# ESP-Live.net
KiCad netlist of a schematic drawn in EAGLE
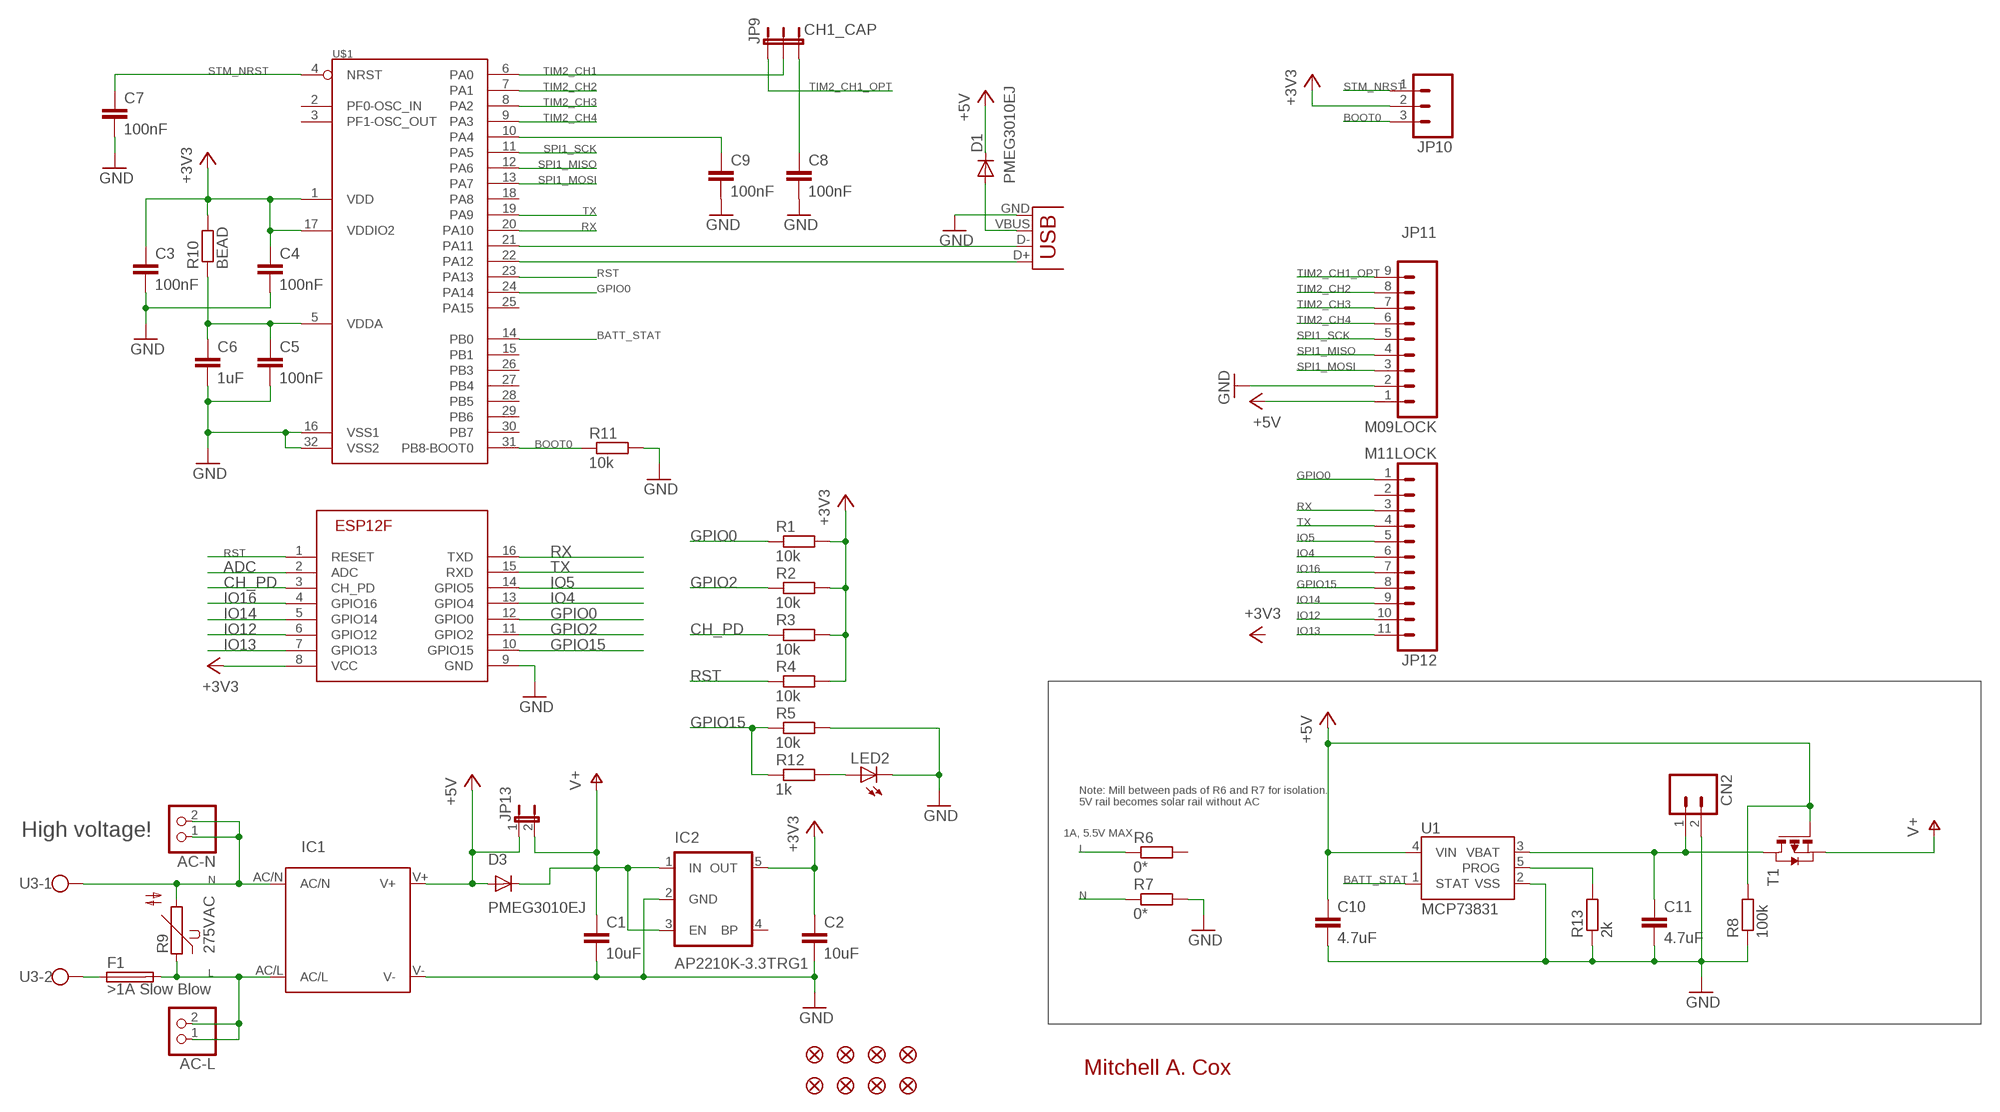
[diagram p0: schematic, sheet 1]

(export (version "E")
  (design (tool "Eeschema 10.0.6"))
  (components
    (comp (ref "AC-L")
      (value "PINHD-1X2")
      (footprint "eagle-import:1X02")
      (libsource (lib "eagle-import") (part "PINHD-1X2"))
    )
    (comp (ref "AC-N")
      (value "PINHD-1X2")
      (footprint "eagle-import:1X02")
      (libsource (lib "eagle-import") (part "PINHD-1X2"))
    )
    (comp (ref "C1")
      (value "10uF")
      (footprint "eagle-import:C0805")
      (libsource (lib "eagle-import") (part "C-EUC0805"))
    )
    (comp (ref "C2")
      (value "10uF")
      (footprint "eagle-import:C0805")
      (libsource (lib "eagle-import") (part "C-EUC0805"))
    )
    (comp (ref "C3")
      (value "100nF")
      (footprint "eagle-import:C0603")
      (libsource (lib "eagle-import") (part "C-EUC0603"))
    )
    (comp (ref "C4")
      (value "100nF")
      (footprint "eagle-import:C0603")
      (libsource (lib "eagle-import") (part "C-EUC0603"))
    )
    (comp (ref "C5")
      (value "100nF")
      (footprint "eagle-import:C0603")
      (libsource (lib "eagle-import") (part "C-EUC0603"))
    )
    (comp (ref "C6")
      (value "1uF")
      (footprint "eagle-import:C0805")
      (libsource (lib "eagle-import") (part "C-EUC0805"))
    )
    (comp (ref "C7")
      (value "100nF")
      (footprint "eagle-import:C0603")
      (libsource (lib "eagle-import") (part "C-EUC0603"))
    )
    (comp (ref "C8")
      (value "100nF")
      (footprint "eagle-import:C0603")
      (libsource (lib "eagle-import") (part "C-EUC0603"))
    )
    (comp (ref "C9")
      (value "100nF")
      (footprint "eagle-import:C0603")
      (libsource (lib "eagle-import") (part "C-EUC0603"))
    )
    (comp (ref "C10")
      (value "4.7uF")
      (footprint "eagle-import:C0805")
      (libsource (lib "eagle-import") (part "C-EUC0805"))
    )
    (comp (ref "C11")
      (value "4.7uF")
      (footprint "eagle-import:C0805")
      (libsource (lib "eagle-import") (part "C-EUC0805"))
    )
    (comp (ref "CN1")
      (value "USBSMD")
      (footprint "eagle-import:USB-MINIB")
      (libsource (lib "eagle-import") (part "USBSMD"))
    )
    (comp (ref "CN2")
      (value "M02-JST-2-PTH-NO_SILK")
      (footprint "eagle-import:JST-2-PTH-NS")
      (libsource (lib "eagle-import") (part "M02-JST-2-PTH-NO_SILK"))
    )
    (comp (ref "D1")
      (value "PMEG3010EJ")
      (footprint "eagle-import:SOD-323")
      (libsource (lib "eagle-import") (part "DIODESOD"))
    )
    (comp (ref "D3")
      (value "PMEG3010EJ")
      (footprint "eagle-import:SOD-323")
      (libsource (lib "eagle-import") (part "DIODESOD"))
    )
    (comp (ref "F1")
      (value ">1A Slow Blow")
      (footprint "eagle-import:TE5")
      (libsource (lib "eagle-import") (part "TE5"))
    )
    (comp (ref "IC1")
      (value "IRM_01/02_SMDIRM_01/02_SMD")
      (footprint "eagle-import:IRM_01_02_SMD")
      (libsource (lib "eagle-import") (part "IRM_01/02_SMDIRM_01/02_SMD"))
    )
    (comp (ref "IC2")
      (value "AP2210K-3.3TRG1")
      (footprint "eagle-import:SOT23-5")
      (libsource (lib "eagle-import") (part "V_REG_LDOSMD"))
    )
    (comp (ref "IC3")
      (value "ESP-12F")
      (footprint "eagle-import:ESP-12F")
      (libsource (lib "eagle-import") (part "ESP-12F"))
    )
    (comp (ref "JP1")
      (value "FIDUCIAL1X2")
      (footprint "eagle-import:FIDUCIAL-1X2")
      (libsource (lib "eagle-import") (part "FIDUCIAL1X2"))
    )
    (comp (ref "JP2")
      (value "FIDUCIAL1X2")
      (footprint "eagle-import:FIDUCIAL-1X2")
      (libsource (lib "eagle-import") (part "FIDUCIAL1X2"))
    )
    (comp (ref "JP3")
      (value "FIDUCIAL1X2")
      (footprint "eagle-import:FIDUCIAL-1X2")
      (libsource (lib "eagle-import") (part "FIDUCIAL1X2"))
    )
    (comp (ref "JP4")
      (value "FIDUCIAL1X2")
      (footprint "eagle-import:FIDUCIAL-1X2")
      (libsource (lib "eagle-import") (part "FIDUCIAL1X2"))
    )
    (comp (ref "JP5")
      (value "FIDUCIAL1X2")
      (footprint "eagle-import:FIDUCIAL-1X2")
      (libsource (lib "eagle-import") (part "FIDUCIAL1X2"))
    )
    (comp (ref "JP6")
      (value "FIDUCIAL1X2")
      (footprint "eagle-import:FIDUCIAL-1X2")
      (libsource (lib "eagle-import") (part "FIDUCIAL1X2"))
    )
    (comp (ref "JP7")
      (value "FIDUCIAL1X2")
      (footprint "eagle-import:FIDUCIAL-1X2")
      (libsource (lib "eagle-import") (part "FIDUCIAL1X2"))
    )
    (comp (ref "JP8")
      (value "FIDUCIAL1X2")
      (footprint "eagle-import:FIDUCIAL-1X2")
      (libsource (lib "eagle-import") (part "FIDUCIAL1X2"))
    )
    (comp (ref "JP9")
      (value "CH1_CAP")
      (footprint "eagle-import:SJ_3_PASTE1&2")
      (libsource (lib "eagle-import") (part "JUMPER-31-2"))
    )
    (comp (ref "JP10")
      (value "M03LOCK")
      (footprint "eagle-import:1X03_LOCK")
      (libsource (lib "eagle-import") (part "M03LOCK"))
    )
    (comp (ref "JP11")
      (value "M09LOCK")
      (footprint "eagle-import:1X09_LOCK")
      (libsource (lib "eagle-import") (part "M09LOCK"))
    )
    (comp (ref "JP12")
      (value "M11LOCK")
      (footprint "eagle-import:1X11_LOCK")
      (libsource (lib "eagle-import") (part "M11LOCK"))
    )
    (comp (ref "JP13")
      (value "JUMPER-2SMD-NO")
      (footprint "eagle-import:SJ_2S-NO")
      (libsource (lib "eagle-import") (part "JUMPER-2SMD-NO"))
    )
    (comp (ref "LED2")
      (value "LEDCHIPLED_0805")
      (footprint "eagle-import:CHIPLED_0805")
      (libsource (lib "eagle-import") (part "LEDCHIPLED_0805"))
    )
    (comp (ref "R1")
      (value "10k")
      (footprint "eagle-import:R0603")
      (libsource (lib "eagle-import") (part "R-EU_R0603"))
    )
    (comp (ref "R2")
      (value "10k")
      (footprint "eagle-import:R0603")
      (libsource (lib "eagle-import") (part "R-EU_R0603"))
    )
    (comp (ref "R3")
      (value "10k")
      (footprint "eagle-import:R0603")
      (libsource (lib "eagle-import") (part "R-EU_R0603"))
    )
    (comp (ref "R4")
      (value "10k")
      (footprint "eagle-import:R0603")
      (libsource (lib "eagle-import") (part "R-EU_R0603"))
    )
    (comp (ref "R5")
      (value "10k")
      (footprint "eagle-import:R0603")
      (libsource (lib "eagle-import") (part "R-EU_R0603"))
    )
    (comp (ref "R6")
      (value "0*")
      (footprint "eagle-import:R2512")
      (libsource (lib "eagle-import") (part "R-EU_R2512"))
    )
    (comp (ref "R7")
      (value "0*")
      (footprint "eagle-import:R2512")
      (libsource (lib "eagle-import") (part "R-EU_R2512"))
    )
    (comp (ref "R8")
      (value "100k")
      (footprint "eagle-import:R0603")
      (libsource (lib "eagle-import") (part "R-EU_R0603"))
    )
    (comp (ref "R9")
      (value "275VAC")
      (footprint "eagle-import:P593")
      (libsource (lib "eagle-import") (part "P593"))
    )
    (comp (ref "R10")
      (value "BEAD")
      (footprint "eagle-import:R0603")
      (libsource (lib "eagle-import") (part "R-EU_R0603"))
    )
    (comp (ref "R11")
      (value "10k")
      (footprint "eagle-import:R0603")
      (libsource (lib "eagle-import") (part "R-EU_R0603"))
    )
    (comp (ref "R12")
      (value "1k")
      (footprint "eagle-import:R0603")
      (libsource (lib "eagle-import") (part "R-EU_R0603"))
    )
    (comp (ref "R13")
      (value "2k")
      (footprint "eagle-import:R0603")
      (libsource (lib "eagle-import") (part "R-EU_R0603"))
    )
    (comp (ref "T1")
      (value "PMOSSOT23")
      (footprint "eagle-import:SOT-23")
      (libsource (lib "eagle-import") (part "PMOSSOT23"))
    )
    (comp (ref "U$1")
      (value "STM32F042K")
      (footprint "eagle-import:LQFP32")
      (libsource (lib "eagle-import") (part "STM32F042K"))
    )
    (comp (ref "U1")
      (value "MCP73831")
      (footprint "eagle-import:SOT23-5")
      (libsource (lib "eagle-import") (part "MCP73831"))
    )
    (comp (ref "U3")
      (value "W237-102")
      (footprint "eagle-import:W237-102")
      (fields (field (name "MPN") "237-102"))
      (libsource (lib "eagle-import") (part "W237-102"))
    )
  )
  (nets
    (net (code "1") (name "+3V3") (class "Default")
      (node (ref "C2") (pin "1") (pinfunction "1_1") (pintype "passive"))
      (node (ref "C3") (pin "1") (pinfunction "1_1") (pintype "passive"))
      (node (ref "C4") (pin "1") (pinfunction "1_1") (pintype "passive"))
      (node (ref "IC2") (pin "5") (pinfunction "OUT_5") (pintype "passive"))
      (node (ref "IC3") (pin "8") (pinfunction "VCC_8") (pintype "power_in"))
      (node (ref "JP10") (pin "2") (pinfunction "2_2") (pintype "passive"))
      (node (ref "R1") (pin "2") (pinfunction "2_2") (pintype "passive"))
      (node (ref "R10") (pin "2") (pinfunction "2_2") (pintype "passive"))
      (node (ref "R2") (pin "2") (pinfunction "2_2") (pintype "passive"))
      (node (ref "R3") (pin "2") (pinfunction "2_2") (pintype "passive"))
      (node (ref "R4") (pin "2") (pinfunction "2_2") (pintype "passive"))
      (node (ref "U$1") (pin "1") (pinfunction "VDD_1") (pintype "power_in"))
      (node (ref "U$1") (pin "17") (pinfunction "VDDIO2_17") (pintype "power_in"))
    )
    (net (code "2") (name "+5V") (class "Default")
      (node (ref "C10") (pin "1") (pinfunction "1_1") (pintype "passive"))
      (node (ref "D1") (pin "1") (pinfunction "C_1") (pintype "passive"))
      (node (ref "D3") (pin "2") (pinfunction "A_2") (pintype "passive"))
      (node (ref "IC1") (pin "V+") (pinfunction "V+_V+") (pintype "output"))
      (node (ref "JP11") (pin "1") (pinfunction "1_1") (pintype "passive"))
      (node (ref "JP13") (pin "1") (pinfunction "1_1") (pintype "passive"))
      (node (ref "R8") (pin "2") (pinfunction "2_2") (pintype "passive"))
      (node (ref "T1") (pin "3") (pinfunction "G_3") (pintype "passive"))
      (node (ref "U1") (pin "4") (pinfunction "VIN_4") (pintype "power_in"))
    )
    (net (code "3") (name "/ADC") (class "Default")
      (node (ref "IC3") (pin "2") (pinfunction "ADC_2") (pintype "passive"))
    )
    (net (code "4") (name "/BATT_STAT") (class "Default")
      (node (ref "U$1") (pin "14") (pinfunction "PB0_14") (pintype "bidirectional"))
      (node (ref "U1") (pin "1") (pinfunction "STAT_1") (pintype "output"))
    )
    (net (code "5") (name "/BOOT0") (class "Default")
      (node (ref "JP10") (pin "3") (pinfunction "3_3") (pintype "passive"))
      (node (ref "R11") (pin "1") (pinfunction "1_1") (pintype "passive"))
      (node (ref "U$1") (pin "31") (pinfunction "PB8-BOOT0_31") (pintype "bidirectional"))
    )
    (net (code "6") (name "/CH_PD") (class "Default")
      (node (ref "IC3") (pin "3") (pinfunction "CH_PD_3") (pintype "input"))
      (node (ref "R3") (pin "1") (pinfunction "1_1") (pintype "passive"))
    )
    (net (code "7") (name "/GPIO0") (class "Default")
      (node (ref "IC3") (pin "12") (pinfunction "GPIO0_12") (pintype "bidirectional"))
      (node (ref "JP12") (pin "1") (pinfunction "1_1") (pintype "passive"))
      (node (ref "R1") (pin "1") (pinfunction "1_1") (pintype "passive"))
      (node (ref "U$1") (pin "24") (pinfunction "PA14_24") (pintype "bidirectional"))
    )
    (net (code "8") (name "/GPIO2") (class "Default")
      (node (ref "IC3") (pin "11") (pinfunction "GPIO2_11") (pintype "bidirectional"))
      (node (ref "R2") (pin "1") (pinfunction "1_1") (pintype "passive"))
    )
    (net (code "9") (name "/GPIO15") (class "Default")
      (node (ref "IC3") (pin "10") (pinfunction "GPIO15_10") (pintype "bidirectional"))
      (node (ref "JP12") (pin "8") (pinfunction "8_8") (pintype "passive"))
      (node (ref "R12") (pin "1") (pinfunction "1_1") (pintype "passive"))
      (node (ref "R5") (pin "1") (pinfunction "1_1") (pintype "passive"))
    )
    (net (code "10") (name "/IO4") (class "Default")
      (node (ref "IC3") (pin "13") (pinfunction "GPIO4_13") (pintype "bidirectional"))
      (node (ref "JP12") (pin "6") (pinfunction "6_6") (pintype "passive"))
    )
    (net (code "11") (name "/IO5") (class "Default")
      (node (ref "IC3") (pin "14") (pinfunction "GPIO5_14") (pintype "bidirectional"))
      (node (ref "JP12") (pin "5") (pinfunction "5_5") (pintype "passive"))
    )
    (net (code "12") (name "/IO12") (class "Default")
      (node (ref "IC3") (pin "6") (pinfunction "GPIO12_6") (pintype "bidirectional"))
      (node (ref "JP12") (pin "10") (pinfunction "10_10") (pintype "passive"))
    )
    (net (code "13") (name "/IO13") (class "Default")
      (node (ref "IC3") (pin "7") (pinfunction "GPIO13_7") (pintype "bidirectional"))
      (node (ref "JP12") (pin "11") (pinfunction "11_11") (pintype "passive"))
    )
    (net (code "14") (name "/IO14") (class "Default")
      (node (ref "IC3") (pin "5") (pinfunction "GPIO14_5") (pintype "bidirectional"))
      (node (ref "JP12") (pin "9") (pinfunction "9_9") (pintype "passive"))
    )
    (net (code "15") (name "/IO16") (class "Default")
      (node (ref "IC3") (pin "4") (pinfunction "GPIO16_4") (pintype "bidirectional"))
      (node (ref "JP12") (pin "7") (pinfunction "7_7") (pintype "passive"))
    )
    (net (code "16") (name "/L") (class "Default")
      (node (ref "AC-L") (pin "1") (pinfunction "1_1") (pintype "passive"))
      (node (ref "AC-L") (pin "2") (pinfunction "2_2") (pintype "passive"))
      (node (ref "F1") (pin "2") (pinfunction "2_2") (pintype "passive"))
      (node (ref "IC1") (pin "AC/L") (pinfunction "AC/L_AC/L") (pintype "input"))
      (node (ref "R6") (pin "1") (pinfunction "1_1") (pintype "passive"))
      (node (ref "R9") (pin "1") (pinfunction "1_1") (pintype "passive"))
    )
    (net (code "17") (name "/N") (class "Default")
      (node (ref "AC-N") (pin "1") (pinfunction "1_1") (pintype "passive"))
      (node (ref "AC-N") (pin "2") (pinfunction "2_2") (pintype "passive"))
      (node (ref "IC1") (pin "AC/N") (pinfunction "AC/N_AC/N") (pintype "input"))
      (node (ref "R7") (pin "1") (pinfunction "1_1") (pintype "passive"))
      (node (ref "R9") (pin "2") (pinfunction "2_2") (pintype "passive"))
      (node (ref "U3") (pin "1") (pinfunction "KL_1") (pintype "passive"))
    )
    (net (code "18") (name "/RST") (class "Default")
      (node (ref "IC3") (pin "1") (pinfunction "RESET_1") (pintype "input"))
      (node (ref "R4") (pin "1") (pinfunction "1_1") (pintype "passive"))
      (node (ref "U$1") (pin "23") (pinfunction "PA13_23") (pintype "bidirectional"))
    )
    (net (code "19") (name "/RX") (class "Default")
      (node (ref "IC3") (pin "16") (pinfunction "TXD_16") (pintype "output"))
      (node (ref "JP12") (pin "3") (pinfunction "3_3") (pintype "passive"))
      (node (ref "U$1") (pin "20") (pinfunction "PA10_20") (pintype "bidirectional"))
    )
    (net (code "20") (name "/SPI1_MISO") (class "Default")
      (node (ref "JP11") (pin "4") (pinfunction "4_4") (pintype "passive"))
      (node (ref "U$1") (pin "12") (pinfunction "PA6_12") (pintype "bidirectional"))
    )
    (net (code "21") (name "/SPI1_MOSI") (class "Default")
      (node (ref "JP11") (pin "3") (pinfunction "3_3") (pintype "passive"))
      (node (ref "U$1") (pin "13") (pinfunction "PA7_13") (pintype "bidirectional"))
    )
    (net (code "22") (name "/SPI1_SCK") (class "Default")
      (node (ref "JP11") (pin "5") (pinfunction "5_5") (pintype "passive"))
      (node (ref "U$1") (pin "11") (pinfunction "PA5_11") (pintype "bidirectional"))
    )
    (net (code "23") (name "/STM_NRST") (class "Default")
      (node (ref "C7") (pin "1") (pinfunction "1_1") (pintype "passive"))
      (node (ref "JP10") (pin "1") (pinfunction "1_1") (pintype "passive"))
      (node (ref "U$1") (pin "4") (pinfunction "NRST_4") (pintype "input"))
    )
    (net (code "24") (name "/TIM2_CH1") (class "Default")
      (node (ref "JP9") (pin "2") (pinfunction "2_2") (pintype "passive"))
      (node (ref "U$1") (pin "6") (pinfunction "PA0_6") (pintype "bidirectional"))
    )
    (net (code "25") (name "/TIM2_CH1_OPT") (class "Default")
      (node (ref "JP11") (pin "9") (pinfunction "9_9") (pintype "passive"))
      (node (ref "JP9") (pin "1") (pinfunction "1_1") (pintype "passive"))
    )
    (net (code "26") (name "/TIM2_CH2") (class "Default")
      (node (ref "JP11") (pin "8") (pinfunction "8_8") (pintype "passive"))
      (node (ref "U$1") (pin "7") (pinfunction "PA1_7") (pintype "bidirectional"))
    )
    (net (code "27") (name "/TIM2_CH3") (class "Default")
      (node (ref "JP11") (pin "7") (pinfunction "7_7") (pintype "passive"))
      (node (ref "U$1") (pin "8") (pinfunction "PA2_8") (pintype "bidirectional"))
    )
    (net (code "28") (name "/TIM2_CH4") (class "Default")
      (node (ref "JP11") (pin "6") (pinfunction "6_6") (pintype "passive"))
      (node (ref "U$1") (pin "9") (pinfunction "PA3_9") (pintype "bidirectional"))
    )
    (net (code "29") (name "/TX") (class "Default")
      (node (ref "IC3") (pin "15") (pinfunction "RXD_15") (pintype "input"))
      (node (ref "JP12") (pin "4") (pinfunction "4_4") (pintype "passive"))
      (node (ref "U$1") (pin "19") (pinfunction "PA9_19") (pintype "bidirectional"))
    )
    (net (code "30") (name "GND") (class "Default")
      (node (ref "C1") (pin "2") (pinfunction "2_2") (pintype "passive"))
      (node (ref "C10") (pin "2") (pinfunction "2_2") (pintype "passive"))
      (node (ref "C11") (pin "2") (pinfunction "2_2") (pintype "passive"))
      (node (ref "C2") (pin "2") (pinfunction "2_2") (pintype "passive"))
      (node (ref "C3") (pin "2") (pinfunction "2_2") (pintype "passive"))
      (node (ref "C4") (pin "2") (pinfunction "2_2") (pintype "passive"))
      (node (ref "C5") (pin "2") (pinfunction "2_2") (pintype "passive"))
      (node (ref "C6") (pin "2") (pinfunction "2_2") (pintype "passive"))
      (node (ref "C7") (pin "2") (pinfunction "2_2") (pintype "passive"))
      (node (ref "C8") (pin "2") (pinfunction "2_2") (pintype "passive"))
      (node (ref "C9") (pin "2") (pinfunction "2_2") (pintype "passive"))
      (node (ref "CN1") (pin "GND") (pinfunction "GND_GND") (pintype "bidirectional"))
      (node (ref "CN2") (pin "2") (pinfunction "2_2") (pintype "passive"))
      (node (ref "IC1") (pin "V-") (pinfunction "V-_V-") (pintype "output"))
      (node (ref "IC2") (pin "2") (pinfunction "GND_2") (pintype "input"))
      (node (ref "IC3") (pin "9") (pinfunction "GND_9") (pintype "power_in"))
      (node (ref "JP11") (pin "2") (pinfunction "2_2") (pintype "passive"))
      (node (ref "LED2") (pin "C") (pinfunction "C_C") (pintype "passive"))
      (node (ref "R11") (pin "2") (pinfunction "2_2") (pintype "passive"))
      (node (ref "R13") (pin "1") (pinfunction "1_1") (pintype "passive"))
      (node (ref "R5") (pin "2") (pinfunction "2_2") (pintype "passive"))
      (node (ref "R7") (pin "2") (pinfunction "2_2") (pintype "passive"))
      (node (ref "R8") (pin "1") (pinfunction "1_1") (pintype "passive"))
      (node (ref "U$1") (pin "16") (pinfunction "VSS1_16") (pintype "power_in"))
      (node (ref "U$1") (pin "32") (pinfunction "VSS2_32") (pintype "power_in"))
      (node (ref "U1") (pin "2") (pinfunction "VSS_2") (pintype "power_in"))
    )
    (net (code "31") (name "Net-(C8-Pad1)") (class "Default")
      (node (ref "C8") (pin "1") (pinfunction "1_1") (pintype "passive"))
      (node (ref "JP9") (pin "3") (pinfunction "3_3") (pintype "passive"))
    )
    (net (code "32") (name "Net-(D1-A)") (class "Default")
      (node (ref "CN1") (pin "VBUS") (pinfunction "VBUS_VBUS") (pintype "bidirectional"))
      (node (ref "D1") (pin "2") (pinfunction "A_2") (pintype "passive"))
    )
    (net (code "33") (name "Net-(LED2-PadA)") (class "Default")
      (node (ref "LED2") (pin "A") (pinfunction "A_A") (pintype "passive"))
      (node (ref "R12") (pin "2") (pinfunction "2_2") (pintype "passive"))
    )
    (net (code "34") (name "Net-(T1-D)") (class "Default")
      (node (ref "C11") (pin "1") (pinfunction "1_1") (pintype "passive"))
      (node (ref "CN2") (pin "1") (pinfunction "1_1") (pintype "passive"))
      (node (ref "T1") (pin "1") (pinfunction "D_1") (pintype "passive"))
      (node (ref "U1") (pin "3") (pinfunction "VBAT_3") (pintype "power_in"))
    )
    (net (code "35") (name "Net-(U$1-PA4)") (class "Default")
      (node (ref "C9") (pin "1") (pinfunction "1_1") (pintype "passive"))
      (node (ref "U$1") (pin "10") (pinfunction "PA4_10") (pintype "bidirectional"))
    )
    (net (code "36") (name "Net-(U$1-PA11)") (class "Default")
      (node (ref "CN1") (pin "D-") (pinfunction "D-_D-") (pintype "bidirectional"))
      (node (ref "U$1") (pin "21") (pinfunction "PA11_21") (pintype "bidirectional"))
    )
    (net (code "37") (name "Net-(U$1-PA12)") (class "Default")
      (node (ref "CN1") (pin "D+") (pinfunction "D+_D+") (pintype "bidirectional"))
      (node (ref "U$1") (pin "22") (pinfunction "PA12_22") (pintype "bidirectional"))
    )
    (net (code "38") (name "Net-(U$1-VDDA)") (class "Default")
      (node (ref "C5") (pin "1") (pinfunction "1_1") (pintype "passive"))
      (node (ref "C6") (pin "1") (pinfunction "1_1") (pintype "passive"))
      (node (ref "R10") (pin "1") (pinfunction "1_1") (pintype "passive"))
      (node (ref "U$1") (pin "5") (pinfunction "VDDA_5") (pintype "power_in"))
    )
    (net (code "39") (name "Net-(U1-PROG)") (class "Default")
      (node (ref "R13") (pin "2") (pinfunction "2_2") (pintype "passive"))
      (node (ref "U1") (pin "5") (pinfunction "PROG_5") (pintype "input"))
    )
    (net (code "40") (name "Net-(U3B-KL)") (class "Default")
      (node (ref "F1") (pin "1") (pinfunction "1_1") (pintype "passive"))
      (node (ref "U3") (pin "2") (pinfunction "KL_2") (pintype "passive"))
    )
    (net (code "41") (name "V+") (class "Default")
      (node (ref "C1") (pin "1") (pinfunction "1_1") (pintype "passive"))
      (node (ref "D3") (pin "1") (pinfunction "C_1") (pintype "passive"))
      (node (ref "IC2") (pin "1") (pinfunction "IN_1") (pintype "input"))
      (node (ref "IC2") (pin "3") (pinfunction "EN_3") (pintype "input"))
      (node (ref "JP13") (pin "2") (pinfunction "2_2") (pintype "passive"))
      (node (ref "T1") (pin "2") (pinfunction "S_2") (pintype "passive"))
    )
    (net (code "42") (name "unconnected-(IC2-BP-Pad4)") (class "Default")
      (node (ref "IC2") (pin "4") (pinfunction "BP_4") (pintype "input"))
    )
    (net (code "43") (name "unconnected-(JP12-Pad2)") (class "Default")
      (node (ref "JP12") (pin "2") (pinfunction "2_2") (pintype "passive"))
    )
    (net (code "44") (name "unconnected-(R6-Pad2)") (class "Default")
      (node (ref "R6") (pin "2") (pinfunction "2_2") (pintype "passive"))
    )
    (net (code "45") (name "unconnected-(U$1-PA8-Pad18)") (class "Default")
      (node (ref "U$1") (pin "18") (pinfunction "PA8_18") (pintype "bidirectional"))
    )
    (net (code "46") (name "unconnected-(U$1-PA15-Pad25)") (class "Default")
      (node (ref "U$1") (pin "25") (pinfunction "PA15_25") (pintype "bidirectional"))
    )
    (net (code "47") (name "unconnected-(U$1-PB1-Pad15)") (class "Default")
      (node (ref "U$1") (pin "15") (pinfunction "PB1_15") (pintype "bidirectional"))
    )
    (net (code "48") (name "unconnected-(U$1-PB3-Pad26)") (class "Default")
      (node (ref "U$1") (pin "26") (pinfunction "PB3_26") (pintype "bidirectional"))
    )
    (net (code "49") (name "unconnected-(U$1-PB4-Pad27)") (class "Default")
      (node (ref "U$1") (pin "27") (pinfunction "PB4_27") (pintype "bidirectional"))
    )
    (net (code "50") (name "unconnected-(U$1-PB5-Pad28)") (class "Default")
      (node (ref "U$1") (pin "28") (pinfunction "PB5_28") (pintype "bidirectional"))
    )
    (net (code "51") (name "unconnected-(U$1-PB6-Pad29)") (class "Default")
      (node (ref "U$1") (pin "29") (pinfunction "PB6_29") (pintype "bidirectional"))
    )
    (net (code "52") (name "unconnected-(U$1-PB7-Pad30)") (class "Default")
      (node (ref "U$1") (pin "30") (pinfunction "PB7_30") (pintype "bidirectional"))
    )
    (net (code "53") (name "unconnected-(U$1-PF0-OSC_IN-Pad2)") (class "Default")
      (node (ref "U$1") (pin "2") (pinfunction "PF0-OSC_IN_2") (pintype "bidirectional"))
    )
    (net (code "54") (name "unconnected-(U$1-PF1-OSC_OUT-Pad3)") (class "Default")
      (node (ref "U$1") (pin "3") (pinfunction "PF1-OSC_OUT_3") (pintype "bidirectional"))
    )
  )
)
